# Interface_ETH.net
KiCad netlist of a schematic drawn in EAGLE
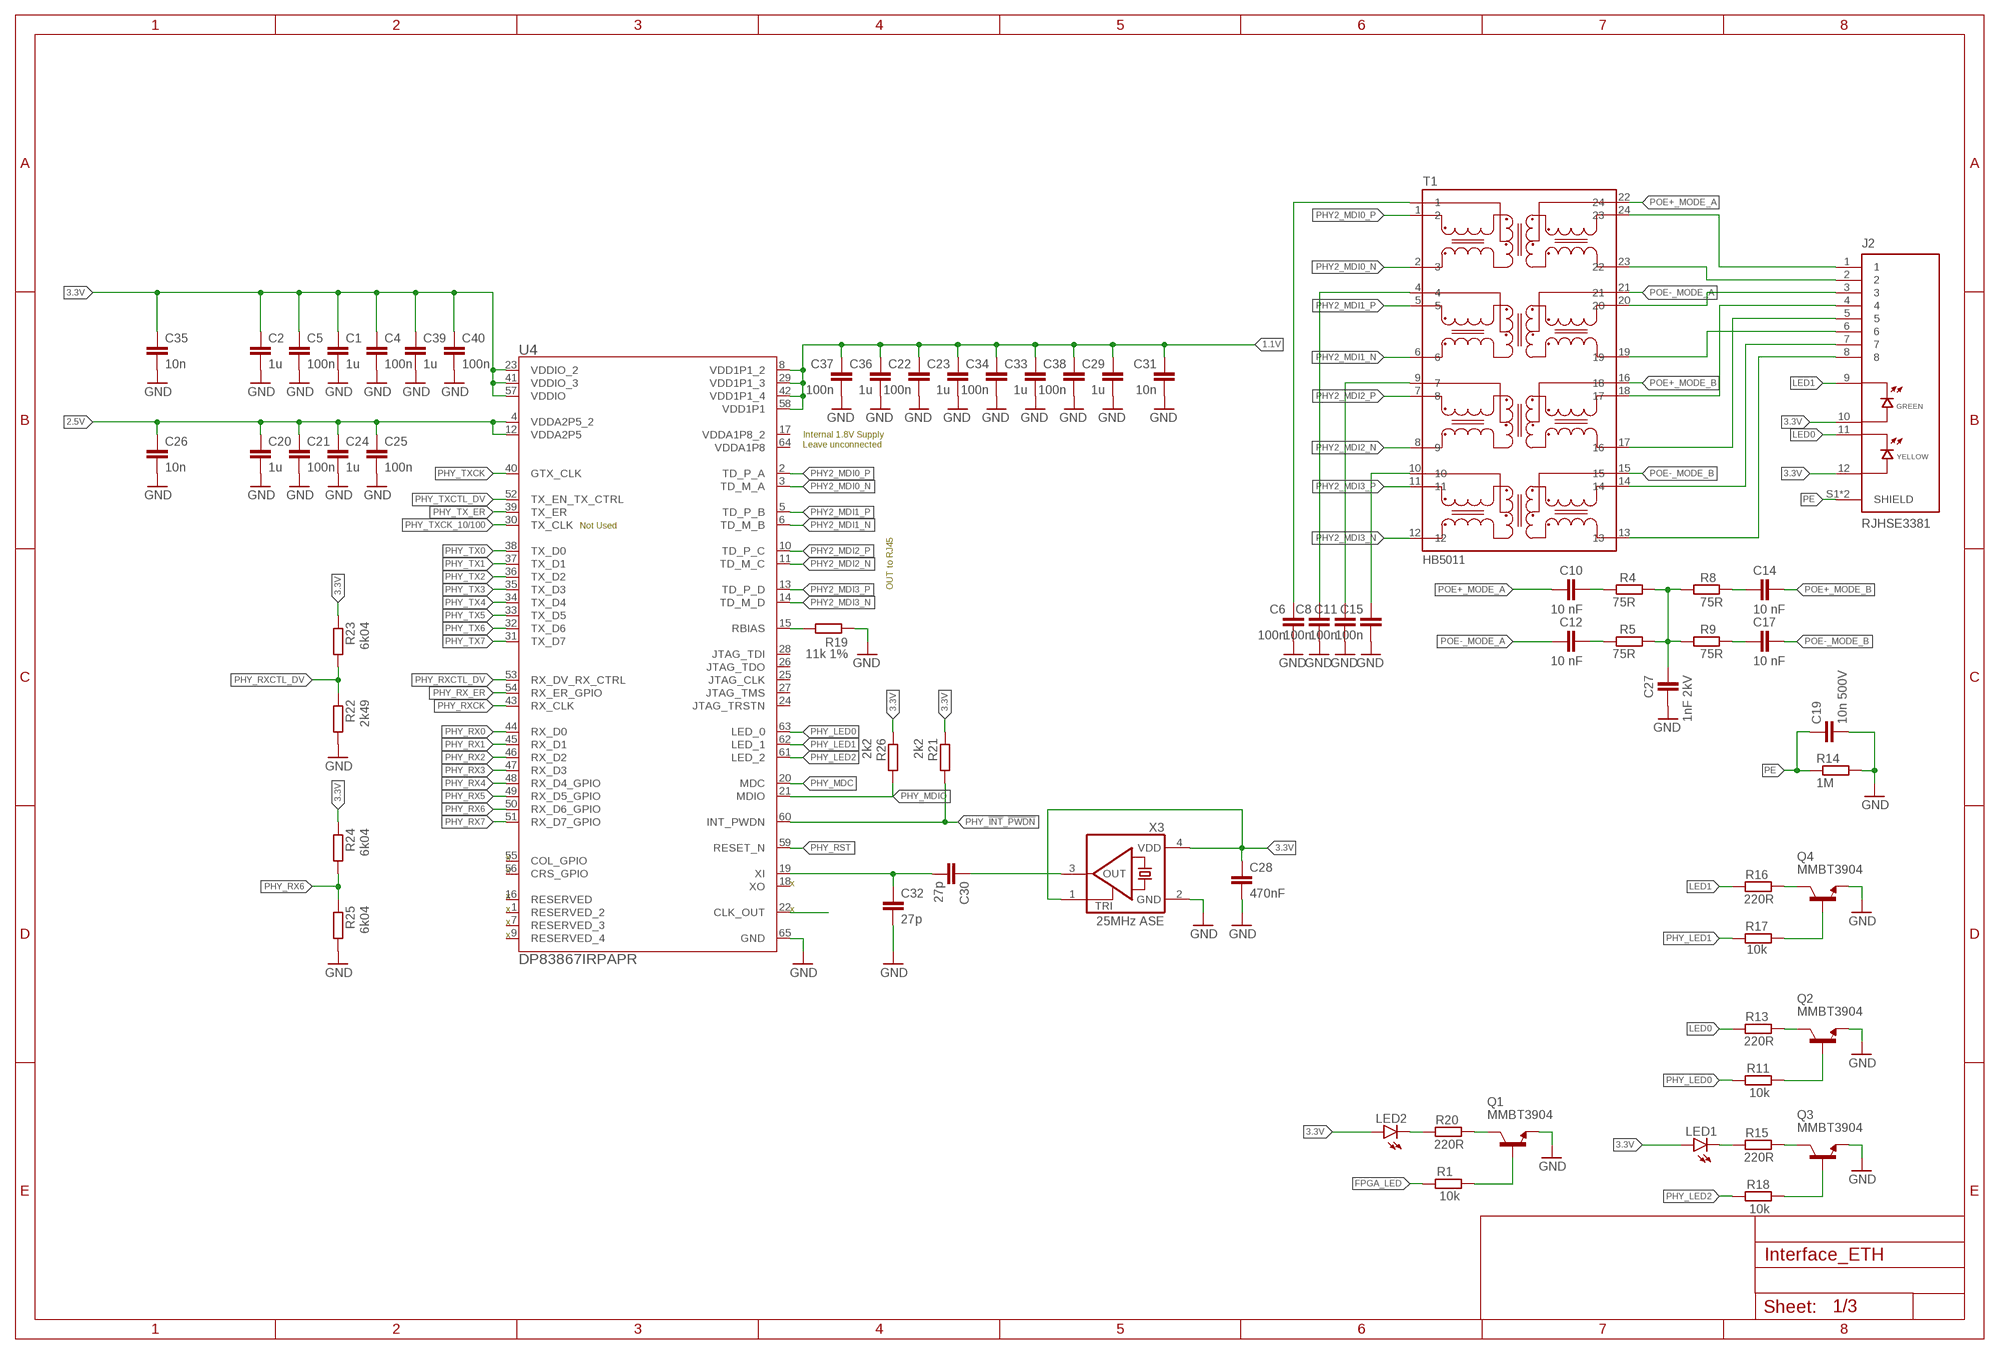
[diagram p0: schematic, sheet 1]
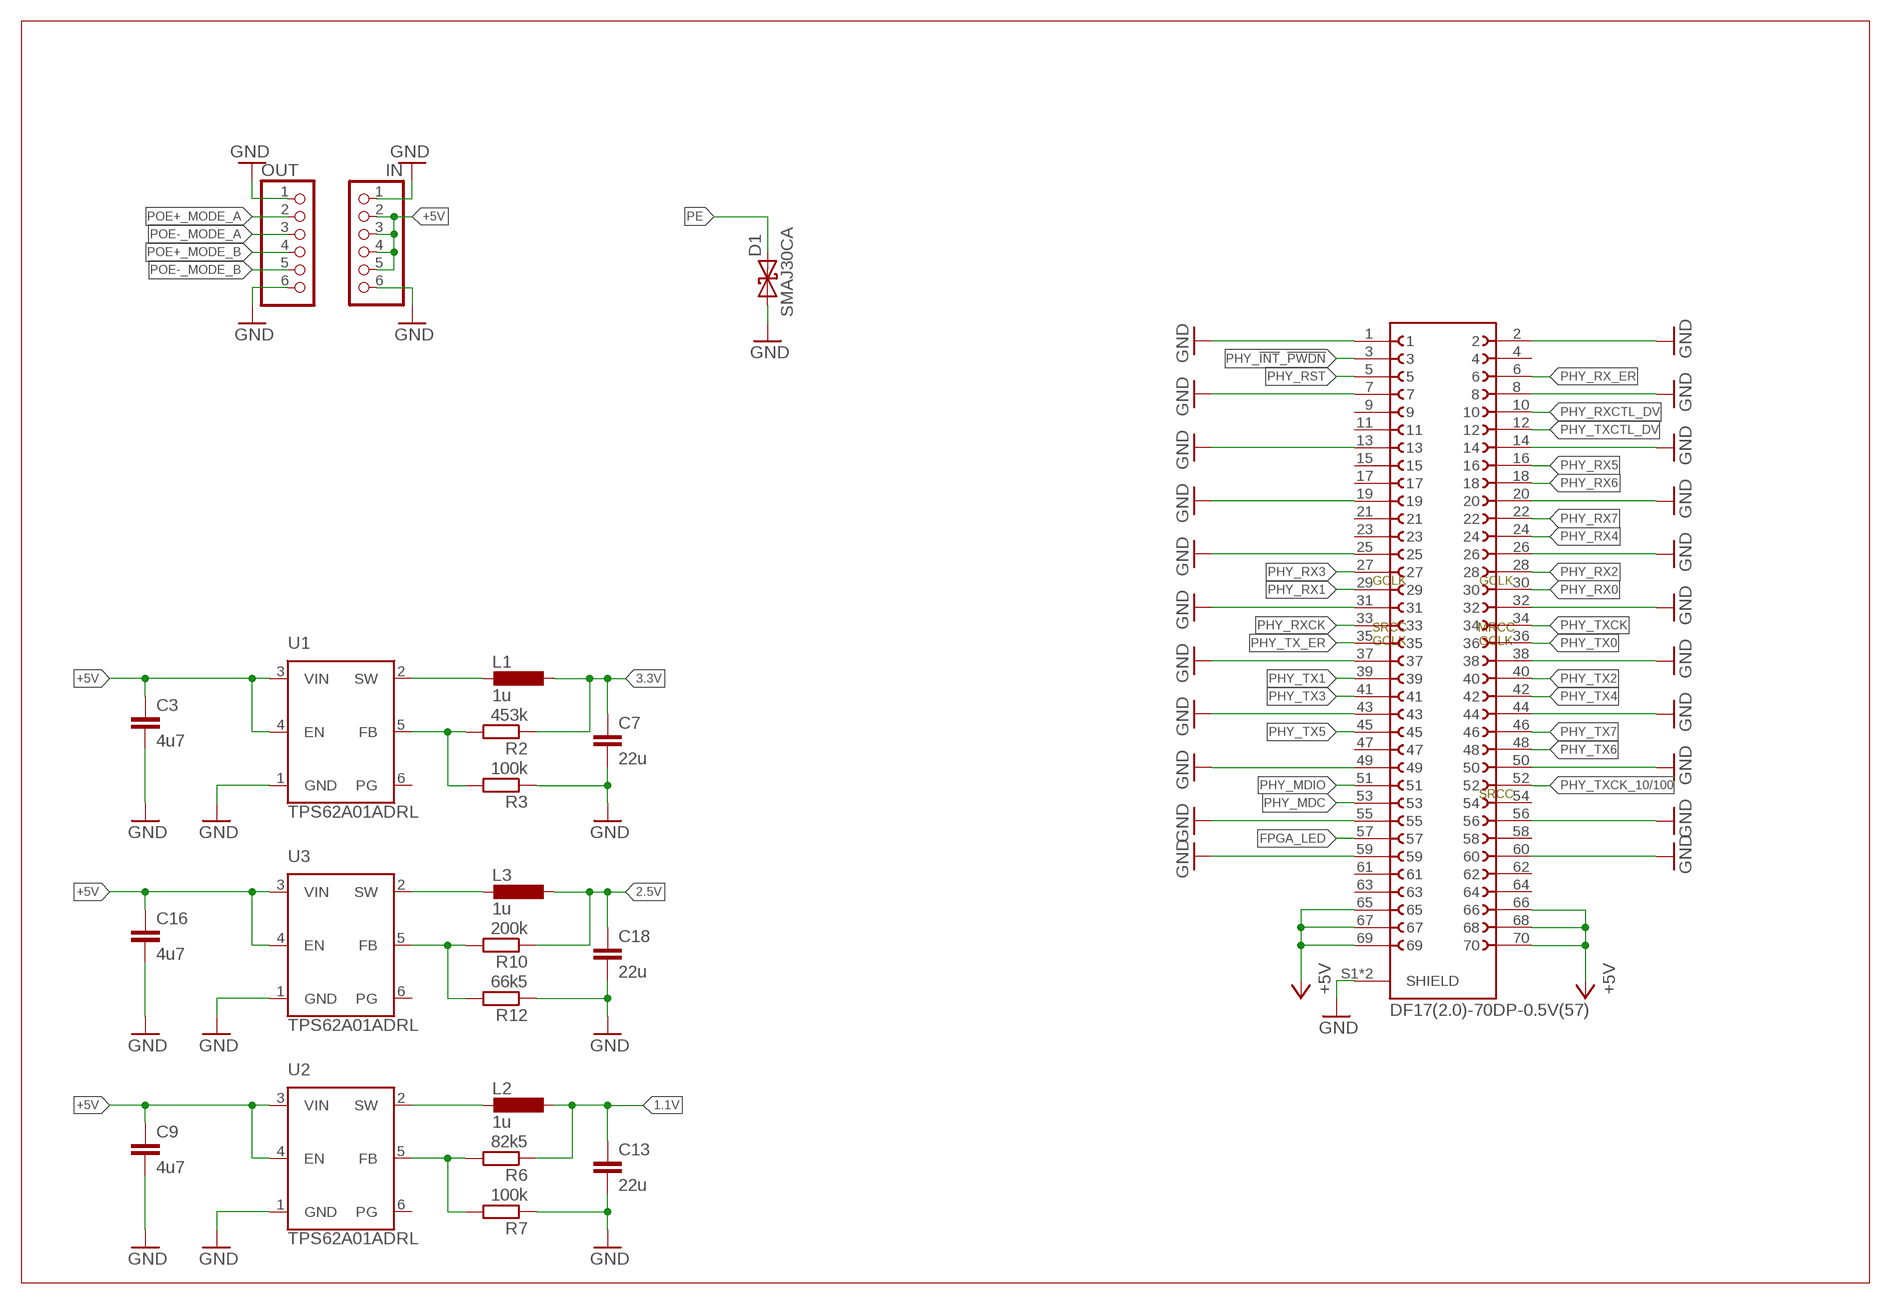
[diagram p1: schematic, sheet 2]

(export (version "E")
  (design (tool "Eeschema 10.0.6"))
  (components
    (comp (ref "C3")
      (value "4u7")
      (footprint "eagle-import:C0603")
      (libsource (lib "eagle-import") (part "C-EUC0603"))
    )
    (comp (ref "C7")
      (value "22u")
      (footprint "eagle-import:C0603")
      (libsource (lib "eagle-import") (part "C-EUC0603"))
    )
    (comp (ref "C9")
      (value "4u7")
      (footprint "eagle-import:C0603")
      (libsource (lib "eagle-import") (part "C-EUC0603"))
    )
    (comp (ref "C13")
      (value "22u")
      (footprint "eagle-import:C0603")
      (libsource (lib "eagle-import") (part "C-EUC0603"))
    )
    (comp (ref "C16")
      (value "4u7")
      (footprint "eagle-import:C0603")
      (libsource (lib "eagle-import") (part "C-EUC0603"))
    )
    (comp (ref "C18")
      (value "22u")
      (footprint "eagle-import:C0603")
      (libsource (lib "eagle-import") (part "C-EUC0603"))
    )
    (comp (ref "D1")
      (value "SMAJ30CA")
      (footprint "eagle-import:DO214AC")
      (libsource (lib "eagle-import") (part "SMAJ_DIODE"))
    )
    (comp (ref "IN")
      (value "PINHD-1X06_2.00")
      (footprint "eagle-import:1X06M")
      (libsource (lib "eagle-import") (part "PINHD-1X06_2.00"))
    )
    (comp (ref "J1")
      (value "DF17(2.0)-70DP-0.5V(57)")
      (footprint "eagle-import:DF17(2.0)-70DP-0.5V(57)")
      (libsource (lib "eagle-import") (part "DF17(2.0)-70DP-0.5V(57)"))
    )
    (comp (ref "L1")
      (value "1u")
      (footprint "eagle-import:L1008")
      (fields (field (name "MPN") "LQM2HPN1R0MG0L"))
      (libsource (lib "eagle-import") (part "L-EU1008"))
    )
    (comp (ref "L2")
      (value "1u")
      (footprint "eagle-import:L1008")
      (fields (field (name "MPN") "LQM2HPN1R0MG0L"))
      (libsource (lib "eagle-import") (part "L-EU1008"))
    )
    (comp (ref "L3")
      (value "1u")
      (footprint "eagle-import:L1008")
      (fields (field (name "MPN") "LQM2HPN1R0MG0L"))
      (libsource (lib "eagle-import") (part "L-EU1008"))
    )
    (comp (ref "OUT")
      (value "PINHD-1X06_2.00")
      (footprint "eagle-import:1X06M")
      (libsource (lib "eagle-import") (part "PINHD-1X06_2.00"))
    )
    (comp (ref "R2")
      (value "453k")
      (footprint "eagle-import:R0402")
      (libsource (lib "eagle-import") (part "rcl_334_R-EU_R0402"))
    )
    (comp (ref "R3")
      (value "100k")
      (footprint "eagle-import:R0402")
      (libsource (lib "eagle-import") (part "rcl_334_R-EU_R0402"))
    )
    (comp (ref "R6")
      (value "82k5")
      (footprint "eagle-import:R0402")
      (libsource (lib "eagle-import") (part "rcl_334_R-EU_R0402"))
    )
    (comp (ref "R7")
      (value "100k")
      (footprint "eagle-import:R0402")
      (libsource (lib "eagle-import") (part "rcl_334_R-EU_R0402"))
    )
    (comp (ref "R10")
      (value "200k")
      (footprint "eagle-import:R0402")
      (libsource (lib "eagle-import") (part "rcl_334_R-EU_R0402"))
    )
    (comp (ref "R12")
      (value "66k5")
      (footprint "eagle-import:R0402")
      (libsource (lib "eagle-import") (part "rcl_334_R-EU_R0402"))
    )
    (comp (ref "U1")
      (value "TPS62A01ADRL")
      (footprint "eagle-import:SOTFL50P160X60-6N")
      (fields (field (name "MANUFACTURER_PART_NUMBER") "TPS62A01ADRLR"))
      (libsource (lib "eagle-import") (part "TPS62A01ADRL"))
    )
    (comp (ref "U2")
      (value "TPS62A01ADRL")
      (footprint "eagle-import:SOTFL50P160X60-6N")
      (fields (field (name "MANUFACTURER_PART_NUMBER") "TPS62A01ADRLR"))
      (libsource (lib "eagle-import") (part "TPS62A01ADRL"))
    )
    (comp (ref "U3")
      (value "TPS62A01ADRL")
      (footprint "eagle-import:SOTFL50P160X60-6N")
      (fields (field (name "MANUFACTURER_PART_NUMBER") "TPS62A01ADRLR"))
      (libsource (lib "eagle-import") (part "TPS62A01ADRL"))
    )
    (comp (ref "C1")
      (value "1u")
      (footprint "eagle-import:C0402")
      (libsource (lib "eagle-import") (part "C-EUC0402"))
    )
    (comp (ref "C2")
      (value "1u")
      (footprint "eagle-import:C0402")
      (libsource (lib "eagle-import") (part "C-EUC0402"))
    )
    (comp (ref "C4")
      (value "100n")
      (footprint "eagle-import:C0402")
      (libsource (lib "eagle-import") (part "C-EUC0402"))
    )
    (comp (ref "C5")
      (value "100n")
      (footprint "eagle-import:C0402")
      (libsource (lib "eagle-import") (part "C-EUC0402"))
    )
    (comp (ref "C6")
      (value "100n")
      (footprint "eagle-import:C0402")
      (libsource (lib "eagle-import") (part "C-EUC0402"))
    )
    (comp (ref "C8")
      (value "100n")
      (footprint "eagle-import:C0402")
      (libsource (lib "eagle-import") (part "C-EUC0402"))
    )
    (comp (ref "C10")
      (value "10 nF")
      (footprint "eagle-import:C0603")
      (libsource (lib "eagle-import") (part "rcl_334_C-EUC0603"))
    )
    (comp (ref "C11")
      (value "100n")
      (footprint "eagle-import:C0402")
      (libsource (lib "eagle-import") (part "C-EUC0402"))
    )
    (comp (ref "C12")
      (value "10 nF")
      (footprint "eagle-import:C0603")
      (libsource (lib "eagle-import") (part "rcl_334_C-EUC0603"))
    )
    (comp (ref "C14")
      (value "10 nF")
      (footprint "eagle-import:C0603")
      (libsource (lib "eagle-import") (part "rcl_334_C-EUC0603"))
    )
    (comp (ref "C15")
      (value "100n")
      (footprint "eagle-import:C0402")
      (libsource (lib "eagle-import") (part "C-EUC0402"))
    )
    (comp (ref "C17")
      (value "10 nF")
      (footprint "eagle-import:C0603")
      (libsource (lib "eagle-import") (part "rcl_334_C-EUC0603"))
    )
    (comp (ref "C19")
      (value "10n 500V")
      (footprint "eagle-import:C0805")
      (libsource (lib "eagle-import") (part "C-EUC0805"))
    )
    (comp (ref "C20")
      (value "1u")
      (footprint "eagle-import:C0402")
      (libsource (lib "eagle-import") (part "C-EUC0402"))
    )
    (comp (ref "C21")
      (value "100n")
      (footprint "eagle-import:C0402")
      (libsource (lib "eagle-import") (part "C-EUC0402"))
    )
    (comp (ref "C22")
      (value "100n")
      (footprint "eagle-import:C0402")
      (libsource (lib "eagle-import") (part "C-EUC0402"))
    )
    (comp (ref "C23")
      (value "1u")
      (footprint "eagle-import:C0402")
      (libsource (lib "eagle-import") (part "C-EUC0402"))
    )
    (comp (ref "C24")
      (value "1u")
      (footprint "eagle-import:C0402")
      (libsource (lib "eagle-import") (part "C-EUC0402"))
    )
    (comp (ref "C25")
      (value "100n")
      (footprint "eagle-import:C0402")
      (libsource (lib "eagle-import") (part "C-EUC0402"))
    )
    (comp (ref "C26")
      (value "10n")
      (footprint "eagle-import:C0402")
      (libsource (lib "eagle-import") (part "C-EUC0402"))
    )
    (comp (ref "C27")
      (value "1nF 2kV")
      (footprint "eagle-import:C1206")
      (libsource (lib "eagle-import") (part "rcl_334_C-EUC1206"))
    )
    (comp (ref "C28")
      (value "470nF")
      (footprint "eagle-import:C0402")
      (libsource (lib "eagle-import") (part "C-EUC0402"))
    )
    (comp (ref "C29")
      (value "1u")
      (footprint "eagle-import:C0402")
      (libsource (lib "eagle-import") (part "C-EUC0402"))
    )
    (comp (ref "C30")
      (value "27p")
      (footprint "eagle-import:C0402")
      (libsource (lib "eagle-import") (part "C-EUC0402"))
    )
    (comp (ref "C31")
      (value "10n")
      (footprint "eagle-import:C0402")
      (libsource (lib "eagle-import") (part "C-EUC0402"))
    )
    (comp (ref "C32")
      (value "27p")
      (footprint "eagle-import:C0402")
      (libsource (lib "eagle-import") (part "C-EUC0402"))
    )
    (comp (ref "C33")
      (value "1u")
      (footprint "eagle-import:C0402")
      (libsource (lib "eagle-import") (part "C-EUC0402"))
    )
    (comp (ref "C34")
      (value "100n")
      (footprint "eagle-import:C0402")
      (libsource (lib "eagle-import") (part "C-EUC0402"))
    )
    (comp (ref "C35")
      (value "10n")
      (footprint "eagle-import:C0402")
      (libsource (lib "eagle-import") (part "C-EUC0402"))
    )
    (comp (ref "C36")
      (value "1u")
      (footprint "eagle-import:C0402")
      (libsource (lib "eagle-import") (part "C-EUC0402"))
    )
    (comp (ref "C37")
      (value "100n")
      (footprint "eagle-import:C0402")
      (libsource (lib "eagle-import") (part "C-EUC0402"))
    )
    (comp (ref "C38")
      (value "100n")
      (footprint "eagle-import:C0402")
      (libsource (lib "eagle-import") (part "C-EUC0402"))
    )
    (comp (ref "C39")
      (value "1u")
      (footprint "eagle-import:C0402")
      (libsource (lib "eagle-import") (part "C-EUC0402"))
    )
    (comp (ref "C40")
      (value "100n")
      (footprint "eagle-import:C0402")
      (libsource (lib "eagle-import") (part "C-EUC0402"))
    )
    (comp (ref "J2")
      (value "RJHSE3381")
      (footprint "eagle-import:AMPHENOL_RJHSE3381")
      (fields (field (name "MANUFACTURER") "Amphenol Connex"))
      (libsource (lib "eagle-import") (part "RJHSE3381"))
    )
    (comp (ref "LED1")
      (value "LEDCHIP-LED0805")
      (footprint "eagle-import:CHIP-LED0805")
      (libsource (lib "eagle-import") (part "LEDCHIP-LED0805"))
    )
    (comp (ref "LED2")
      (value "LEDCHIP-LED0603")
      (footprint "eagle-import:CHIP-LED0603")
      (libsource (lib "eagle-import") (part "LEDCHIP-LED0603"))
    )
    (comp (ref "Q1")
      (value "MMBT3904")
      (footprint "eagle-import:SOT23")
      (libsource (lib "eagle-import") (part "2N3904-MMBT"))
    )
    (comp (ref "Q2")
      (value "MMBT3904")
      (footprint "eagle-import:SOT23")
      (libsource (lib "eagle-import") (part "2N3904-MMBT"))
    )
    (comp (ref "Q3")
      (value "MMBT3904")
      (footprint "eagle-import:SOT23")
      (libsource (lib "eagle-import") (part "2N3904-MMBT"))
    )
    (comp (ref "Q4")
      (value "MMBT3904")
      (footprint "eagle-import:SOT23")
      (libsource (lib "eagle-import") (part "2N3904-MMBT"))
    )
    (comp (ref "R1")
      (value "10k")
      (footprint "eagle-import:R0603")
      (libsource (lib "eagle-import") (part "R-EU_R0603"))
    )
    (comp (ref "R4")
      (value "75R")
      (footprint "eagle-import:R0603")
      (libsource (lib "eagle-import") (part "R-EU_R0603"))
    )
    (comp (ref "R5")
      (value "75R")
      (footprint "eagle-import:R0603")
      (libsource (lib "eagle-import") (part "R-EU_R0603"))
    )
    (comp (ref "R8")
      (value "75R")
      (footprint "eagle-import:R0603")
      (libsource (lib "eagle-import") (part "R-EU_R0603"))
    )
    (comp (ref "R9")
      (value "75R")
      (footprint "eagle-import:R0603")
      (libsource (lib "eagle-import") (part "R-EU_R0603"))
    )
    (comp (ref "R11")
      (value "10k")
      (footprint "eagle-import:R0603")
      (libsource (lib "eagle-import") (part "R-EU_R0603"))
    )
    (comp (ref "R13")
      (value "220R")
      (footprint "eagle-import:R0603")
      (libsource (lib "eagle-import") (part "R-EU_R0603"))
    )
    (comp (ref "R14")
      (value "1M")
      (footprint "eagle-import:R0603")
      (libsource (lib "eagle-import") (part "R-EU_R0603"))
    )
    (comp (ref "R15")
      (value "220R")
      (footprint "eagle-import:R0603")
      (libsource (lib "eagle-import") (part "R-EU_R0603"))
    )
    (comp (ref "R16")
      (value "220R")
      (footprint "eagle-import:R0603")
      (libsource (lib "eagle-import") (part "R-EU_R0603"))
    )
    (comp (ref "R17")
      (value "10k")
      (footprint "eagle-import:R0603")
      (libsource (lib "eagle-import") (part "R-EU_R0603"))
    )
    (comp (ref "R18")
      (value "10k")
      (footprint "eagle-import:R0603")
      (libsource (lib "eagle-import") (part "R-EU_R0603"))
    )
    (comp (ref "R19")
      (value "11k 1%")
      (footprint "eagle-import:R0402")
      (libsource (lib "eagle-import") (part "R-EU_R0402"))
    )
    (comp (ref "R20")
      (value "220R")
      (footprint "eagle-import:R0603")
      (libsource (lib "eagle-import") (part "R-EU_R0603"))
    )
    (comp (ref "R21")
      (value "2k2")
      (footprint "eagle-import:R0402")
      (libsource (lib "eagle-import") (part "R-EU_R0402"))
    )
    (comp (ref "R22")
      (value "2k49")
      (footprint "eagle-import:R0402")
      (libsource (lib "eagle-import") (part "R-EU_R0402"))
    )
    (comp (ref "R23")
      (value "6k04")
      (footprint "eagle-import:R0402")
      (libsource (lib "eagle-import") (part "R-EU_R0402"))
    )
    (comp (ref "R24")
      (value "6k04")
      (footprint "eagle-import:R0402")
      (libsource (lib "eagle-import") (part "R-EU_R0402"))
    )
    (comp (ref "R25")
      (value "6k04")
      (footprint "eagle-import:R0402")
      (libsource (lib "eagle-import") (part "R-EU_R0402"))
    )
    (comp (ref "R26")
      (value "2k2")
      (footprint "eagle-import:R0402")
      (libsource (lib "eagle-import") (part "R-EU_R0402"))
    )
    (comp (ref "T1")
      (value "HB5011")
      (footprint "eagle-import:HB5011")
      (libsource (lib "eagle-import") (part "HB5011"))
    )
    (comp (ref "U4")
      (value "DP83867IRPAPR")
      (footprint "eagle-import:PAP0064M_N")
      (libsource (lib "eagle-import") (part "DP83867IRPAPR"))
    )
    (comp (ref "X3")
      (value "25MHz ASE")
      (footprint "eagle-import:ASE")
      (libsource (lib "eagle-import") (part "ASE"))
    )
  )
  (nets
    (net (code "1") (name "+5V") (class "Default")
      (node (ref "C16") (pin "1") (pinfunction "1_1") (pintype "passive"))
      (node (ref "C3") (pin "1") (pinfunction "1_1") (pintype "passive"))
      (node (ref "C9") (pin "1") (pinfunction "1_1") (pintype "passive"))
      (node (ref "IN") (pin "2") (pinfunction "2_2") (pintype "passive"))
      (node (ref "IN") (pin "3") (pinfunction "3_3") (pintype "passive"))
      (node (ref "IN") (pin "4") (pinfunction "4_4") (pintype "passive"))
      (node (ref "IN") (pin "5") (pinfunction "5_5") (pintype "passive"))
      (node (ref "J1") (pin "65") (pinfunction "65_65") (pintype "passive"))
      (node (ref "J1") (pin "66") (pinfunction "66_66") (pintype "passive"))
      (node (ref "J1") (pin "67") (pinfunction "67_67") (pintype "passive"))
      (node (ref "J1") (pin "68") (pinfunction "68_68") (pintype "passive"))
      (node (ref "J1") (pin "69") (pinfunction "69_69") (pintype "passive"))
      (node (ref "J1") (pin "70") (pinfunction "70_70") (pintype "passive"))
      (node (ref "U1") (pin "3") (pinfunction "VIN_3") (pintype "bidirectional"))
      (node (ref "U1") (pin "4") (pinfunction "EN_4") (pintype "bidirectional"))
      (node (ref "U2") (pin "3") (pinfunction "VIN_3") (pintype "bidirectional"))
      (node (ref "U2") (pin "4") (pinfunction "EN_4") (pintype "bidirectional"))
      (node (ref "U3") (pin "3") (pinfunction "VIN_3") (pintype "bidirectional"))
      (node (ref "U3") (pin "4") (pinfunction "EN_4") (pintype "bidirectional"))
    )
    (net (code "2") (name "1.1V") (class "Default")
      (node (ref "C13") (pin "1") (pinfunction "1_1") (pintype "passive"))
      (node (ref "C22") (pin "1") (pinfunction "1_1") (pintype "passive"))
      (node (ref "C23") (pin "1") (pinfunction "1_1") (pintype "passive"))
      (node (ref "C29") (pin "1") (pinfunction "1_1") (pintype "passive"))
      (node (ref "C31") (pin "1") (pinfunction "1_1") (pintype "passive"))
      (node (ref "C33") (pin "1") (pinfunction "1_1") (pintype "passive"))
      (node (ref "C34") (pin "1") (pinfunction "1_1") (pintype "passive"))
      (node (ref "C36") (pin "1") (pinfunction "1_1") (pintype "passive"))
      (node (ref "C37") (pin "1") (pinfunction "1_1") (pintype "passive"))
      (node (ref "C38") (pin "1") (pinfunction "1_1") (pintype "passive"))
      (node (ref "L2") (pin "1") (pinfunction "1_1") (pintype "passive"))
      (node (ref "R6") (pin "1") (pinfunction "1_1") (pintype "passive"))
      (node (ref "U4") (pin "29") (pinfunction "VDD1P1_3_29") (pintype "power_in"))
      (node (ref "U4") (pin "42") (pinfunction "VDD1P1_4_42") (pintype "power_in"))
      (node (ref "U4") (pin "58") (pinfunction "VDD1P1_58") (pintype "power_in"))
      (node (ref "U4") (pin "8") (pinfunction "VDD1P1_2_8") (pintype "power_in"))
    )
    (net (code "3") (name "2.5V") (class "Default")
      (node (ref "C18") (pin "1") (pinfunction "1_1") (pintype "passive"))
      (node (ref "C20") (pin "1") (pinfunction "1_1") (pintype "passive"))
      (node (ref "C21") (pin "1") (pinfunction "1_1") (pintype "passive"))
      (node (ref "C24") (pin "1") (pinfunction "1_1") (pintype "passive"))
      (node (ref "C25") (pin "1") (pinfunction "1_1") (pintype "passive"))
      (node (ref "C26") (pin "1") (pinfunction "1_1") (pintype "passive"))
      (node (ref "L3") (pin "1") (pinfunction "1_1") (pintype "passive"))
      (node (ref "R10") (pin "1") (pinfunction "1_1") (pintype "passive"))
      (node (ref "U4") (pin "12") (pinfunction "VDDA2P5_12") (pintype "power_in"))
      (node (ref "U4") (pin "4") (pinfunction "VDDA2P5_2_4") (pintype "power_in"))
    )
    (net (code "4") (name "3.3V") (class "Default")
      (node (ref "C1") (pin "1") (pinfunction "1_1") (pintype "passive"))
      (node (ref "C2") (pin "1") (pinfunction "1_1") (pintype "passive"))
      (node (ref "C28") (pin "1") (pinfunction "1_1") (pintype "passive"))
      (node (ref "C35") (pin "1") (pinfunction "1_1") (pintype "passive"))
      (node (ref "C39") (pin "1") (pinfunction "1_1") (pintype "passive"))
      (node (ref "C4") (pin "1") (pinfunction "1_1") (pintype "passive"))
      (node (ref "C40") (pin "1") (pinfunction "1_1") (pintype "passive"))
      (node (ref "C5") (pin "1") (pinfunction "1_1") (pintype "passive"))
      (node (ref "C7") (pin "1") (pinfunction "1_1") (pintype "passive"))
      (node (ref "J2") (pin "10") (pinfunction "10_10") (pintype "passive"))
      (node (ref "J2") (pin "12") (pinfunction "12_12") (pintype "passive"))
      (node (ref "L1") (pin "1") (pinfunction "1_1") (pintype "passive"))
      (node (ref "LED1") (pin "A") (pinfunction "A_A") (pintype "passive"))
      (node (ref "LED2") (pin "A") (pinfunction "A_A") (pintype "passive"))
      (node (ref "R2") (pin "1") (pinfunction "1_1") (pintype "passive"))
      (node (ref "R21") (pin "1") (pinfunction "1_1") (pintype "passive"))
      (node (ref "R23") (pin "1") (pinfunction "1_1") (pintype "passive"))
      (node (ref "R24") (pin "1") (pinfunction "1_1") (pintype "passive"))
      (node (ref "R26") (pin "1") (pinfunction "1_1") (pintype "passive"))
      (node (ref "U4") (pin "23") (pinfunction "VDDIO_2_23") (pintype "power_in"))
      (node (ref "U4") (pin "41") (pinfunction "VDDIO_3_41") (pintype "power_in"))
      (node (ref "U4") (pin "57") (pinfunction "VDDIO_57") (pintype "power_in"))
      (node (ref "X3") (pin "1") (pinfunction "TRI_1") (pintype "input"))
      (node (ref "X3") (pin "4") (pinfunction "VDD_4") (pintype "power_in"))
    )
    (net (code "5") (name "FPGA_LED") (class "Default")
      (node (ref "J1") (pin "57") (pinfunction "57_57") (pintype "passive"))
      (node (ref "R1") (pin "1") (pinfunction "1_1") (pintype "passive"))
    )
    (net (code "6") (name "GND") (class "Default")
      (node (ref "C1") (pin "2") (pinfunction "2_2") (pintype "passive"))
      (node (ref "C11") (pin "2") (pinfunction "2_2") (pintype "passive"))
      (node (ref "C13") (pin "2") (pinfunction "2_2") (pintype "passive"))
      (node (ref "C15") (pin "2") (pinfunction "2_2") (pintype "passive"))
      (node (ref "C16") (pin "2") (pinfunction "2_2") (pintype "passive"))
      (node (ref "C18") (pin "2") (pinfunction "2_2") (pintype "passive"))
      (node (ref "C19") (pin "2") (pinfunction "2_2") (pintype "passive"))
      (node (ref "C2") (pin "2") (pinfunction "2_2") (pintype "passive"))
      (node (ref "C20") (pin "2") (pinfunction "2_2") (pintype "passive"))
      (node (ref "C21") (pin "2") (pinfunction "2_2") (pintype "passive"))
      (node (ref "C22") (pin "2") (pinfunction "2_2") (pintype "passive"))
      (node (ref "C23") (pin "2") (pinfunction "2_2") (pintype "passive"))
      (node (ref "C24") (pin "2") (pinfunction "2_2") (pintype "passive"))
      (node (ref "C25") (pin "2") (pinfunction "2_2") (pintype "passive"))
      (node (ref "C26") (pin "2") (pinfunction "2_2") (pintype "passive"))
      (node (ref "C27") (pin "2") (pinfunction "2_2") (pintype "passive"))
      (node (ref "C28") (pin "2") (pinfunction "2_2") (pintype "passive"))
      (node (ref "C29") (pin "2") (pinfunction "2_2") (pintype "passive"))
      (node (ref "C3") (pin "2") (pinfunction "2_2") (pintype "passive"))
      (node (ref "C31") (pin "2") (pinfunction "2_2") (pintype "passive"))
      (node (ref "C32") (pin "2") (pinfunction "2_2") (pintype "passive"))
      (node (ref "C33") (pin "2") (pinfunction "2_2") (pintype "passive"))
      (node (ref "C34") (pin "2") (pinfunction "2_2") (pintype "passive"))
      (node (ref "C35") (pin "2") (pinfunction "2_2") (pintype "passive"))
      (node (ref "C36") (pin "2") (pinfunction "2_2") (pintype "passive"))
      (node (ref "C37") (pin "2") (pinfunction "2_2") (pintype "passive"))
      (node (ref "C38") (pin "2") (pinfunction "2_2") (pintype "passive"))
      (node (ref "C39") (pin "2") (pinfunction "2_2") (pintype "passive"))
      (node (ref "C4") (pin "2") (pinfunction "2_2") (pintype "passive"))
      (node (ref "C40") (pin "2") (pinfunction "2_2") (pintype "passive"))
      (node (ref "C5") (pin "2") (pinfunction "2_2") (pintype "passive"))
      (node (ref "C6") (pin "2") (pinfunction "2_2") (pintype "passive"))
      (node (ref "C7") (pin "2") (pinfunction "2_2") (pintype "passive"))
      (node (ref "C8") (pin "2") (pinfunction "2_2") (pintype "passive"))
      (node (ref "C9") (pin "2") (pinfunction "2_2") (pintype "passive"))
      (node (ref "D1") (pin "A") (pinfunction "1_A") (pintype "passive"))
      (node (ref "IN") (pin "1") (pinfunction "1_1") (pintype "passive"))
      (node (ref "IN") (pin "6") (pinfunction "6_6") (pintype "passive"))
      (node (ref "J1") (pin "1") (pinfunction "1_1") (pintype "passive"))
      (node (ref "J1") (pin "13") (pinfunction "13_13") (pintype "passive"))
      (node (ref "J1") (pin "14") (pinfunction "14_14") (pintype "passive"))
      (node (ref "J1") (pin "19") (pinfunction "19_19") (pintype "passive"))
      (node (ref "J1") (pin "2") (pinfunction "2_2") (pintype "passive"))
      (node (ref "J1") (pin "20") (pinfunction "20_20") (pintype "passive"))
      (node (ref "J1") (pin "25") (pinfunction "25_25") (pintype "passive"))
      (node (ref "J1") (pin "26") (pinfunction "26_26") (pintype "passive"))
      (node (ref "J1") (pin "31") (pinfunction "31_31") (pintype "passive"))
      (node (ref "J1") (pin "32") (pinfunction "32_32") (pintype "passive"))
      (node (ref "J1") (pin "37") (pinfunction "37_37") (pintype "passive"))
      (node (ref "J1") (pin "38") (pinfunction "38_38") (pintype "passive"))
      (node (ref "J1") (pin "43") (pinfunction "43_43") (pintype "passive"))
      (node (ref "J1") (pin "44") (pinfunction "44_44") (pintype "passive"))
      (node (ref "J1") (pin "49") (pinfunction "49_49") (pintype "passive"))
      (node (ref "J1") (pin "50") (pinfunction "50_50") (pintype "passive"))
      (node (ref "J1") (pin "55") (pinfunction "55_55") (pintype "passive"))
      (node (ref "J1") (pin "56") (pinfunction "56_56") (pintype "passive"))
      (node (ref "J1") (pin "59") (pinfunction "59_59") (pintype "passive"))
      (node (ref "J1") (pin "60") (pinfunction "60_60") (pintype "passive"))
      (node (ref "J1") (pin "7") (pinfunction "7_7") (pintype "passive"))
      (node (ref "J1") (pin "8") (pinfunction "8_8") (pintype "passive"))
      (node (ref "J1") (pin "S1") (pinfunction "SHIELD_S1") (pintype "passive"))
      (node (ref "J1") (pin "S2") (pinfunction "SHIELD_S2") (pintype "passive"))
      (node (ref "OUT") (pin "1") (pinfunction "1_1") (pintype "passive"))
      (node (ref "OUT") (pin "6") (pinfunction "6_6") (pintype "passive"))
      (node (ref "Q1") (pin "2") (pinfunction "E_2") (pintype "passive"))
      (node (ref "Q2") (pin "2") (pinfunction "E_2") (pintype "passive"))
      (node (ref "Q3") (pin "2") (pinfunction "E_2") (pintype "passive"))
      (node (ref "Q4") (pin "2") (pinfunction "E_2") (pintype "passive"))
      (node (ref "R12") (pin "1") (pinfunction "1_1") (pintype "passive"))
      (node (ref "R14") (pin "2") (pinfunction "2_2") (pintype "passive"))
      (node (ref "R19") (pin "1") (pinfunction "1_1") (pintype "passive"))
      (node (ref "R22") (pin "2") (pinfunction "2_2") (pintype "passive"))
      (node (ref "R25") (pin "2") (pinfunction "2_2") (pintype "passive"))
      (node (ref "R3") (pin "1") (pinfunction "1_1") (pintype "passive"))
      (node (ref "R7") (pin "1") (pinfunction "1_1") (pintype "passive"))
      (node (ref "U1") (pin "1") (pinfunction "GND_1") (pintype "bidirectional"))
      (node (ref "U2") (pin "1") (pinfunction "GND_1") (pintype "bidirectional"))
      (node (ref "U3") (pin "1") (pinfunction "GND_1") (pintype "bidirectional"))
      (node (ref "U4") (pin "65") (pinfunction "GND_65") (pintype "power_in"))
      (node (ref "X3") (pin "2") (pinfunction "GND_2") (pintype "power_in"))
    )
    (net (code "7") (name "LED0") (class "Default")
      (node (ref "J2") (pin "11") (pinfunction "11_11") (pintype "passive"))
      (node (ref "R13") (pin "1") (pinfunction "1_1") (pintype "passive"))
    )
    (net (code "8") (name "LED1") (class "Default")
      (node (ref "J2") (pin "9") (pinfunction "9_9") (pintype "passive"))
      (node (ref "R16") (pin "1") (pinfunction "1_1") (pintype "passive"))
    )
    (net (code "9") (name "Net-(C8-Pad1)") (class "Default")
      (node (ref "C8") (pin "1") (pinfunction "1_1") (pintype "passive"))
      (node (ref "T1") (pin "4") (pinfunction "4_4") (pintype "bidirectional"))
    )
    (net (code "10") (name "Net-(C10-Pad1)") (class "Default")
      (node (ref "C10") (pin "1") (pinfunction "1_1") (pintype "passive"))
      (node (ref "R4") (pin "2") (pinfunction "2_2") (pintype "passive"))
    )
    (net (code "11") (name "Net-(C12-Pad1)") (class "Default")
      (node (ref "C12") (pin "1") (pinfunction "1_1") (pintype "passive"))
      (node (ref "R5") (pin "2") (pinfunction "2_2") (pintype "passive"))
    )
    (net (code "12") (name "Net-(C14-Pad1)") (class "Default")
      (node (ref "C14") (pin "1") (pinfunction "1_1") (pintype "passive"))
      (node (ref "R8") (pin "2") (pinfunction "2_2") (pintype "passive"))
    )
    (net (code "13") (name "Net-(C15-Pad1)") (class "Default")
      (node (ref "C15") (pin "1") (pinfunction "1_1") (pintype "passive"))
      (node (ref "T1") (pin "10") (pinfunction "10_10") (pintype "bidirectional"))
    )
    (net (code "14") (name "Net-(C17-Pad1)") (class "Default")
      (node (ref "C17") (pin "1") (pinfunction "1_1") (pintype "passive"))
      (node (ref "R9") (pin "2") (pinfunction "2_2") (pintype "passive"))
    )
    (net (code "15") (name "Net-(C27-Pad1)") (class "Default")
      (node (ref "C27") (pin "1") (pinfunction "1_1") (pintype "passive"))
      (node (ref "R4") (pin "1") (pinfunction "1_1") (pintype "passive"))
      (node (ref "R5") (pin "1") (pinfunction "1_1") (pintype "passive"))
      (node (ref "R8") (pin "1") (pinfunction "1_1") (pintype "passive"))
      (node (ref "R9") (pin "1") (pinfunction "1_1") (pintype "passive"))
    )
    (net (code "16") (name "Net-(J2-Pad3)") (class "Default")
      (node (ref "J2") (pin "3") (pinfunction "3_3") (pintype "passive"))
      (node (ref "T1") (pin "20") (pinfunction "20_20") (pintype "bidirectional"))
    )
    (net (code "17") (name "Net-(J2-Pad6)") (class "Default")
      (node (ref "J2") (pin "6") (pinfunction "6_6") (pintype "passive"))
      (node (ref "T1") (pin "19") (pinfunction "19_19") (pintype "bidirectional"))
    )
    (net (code "18") (name "Net-(J2-Pad7)") (class "Default")
      (node (ref "J2") (pin "7") (pinfunction "7_7") (pintype "passive"))
      (node (ref "T1") (pin "14") (pinfunction "14_14") (pintype "bidirectional"))
    )
    (net (code "19") (name "Net-(J2-Pad8)") (class "Default")
      (node (ref "J2") (pin "8") (pinfunction "8_8") (pintype "passive"))
      (node (ref "T1") (pin "13") (pinfunction "13_13") (pintype "bidirectional"))
    )
    (net (code "20") (name "Net-(LED1-PadC)") (class "Default")
      (node (ref "LED1") (pin "C") (pinfunction "C_C") (pintype "passive"))
      (node (ref "R15") (pin "1") (pinfunction "1_1") (pintype "passive"))
    )
    (net (code "21") (name "Net-(LED2-PadC)") (class "Default")
      (node (ref "LED2") (pin "C") (pinfunction "C_C") (pintype "passive"))
      (node (ref "R20") (pin "1") (pinfunction "1_1") (pintype "passive"))
    )
    (net (code "22") (name "Net-(Q1-B)") (class "Default")
      (node (ref "Q1") (pin "1") (pinfunction "B_1") (pintype "passive"))
      (node (ref "R1") (pin "2") (pinfunction "2_2") (pintype "passive"))
    )
    (net (code "23") (name "Net-(Q1-C)") (class "Default")
      (node (ref "Q1") (pin "3") (pinfunction "C_3") (pintype "passive"))
      (node (ref "R20") (pin "2") (pinfunction "2_2") (pintype "passive"))
    )
    (net (code "24") (name "Net-(Q2-B)") (class "Default")
      (node (ref "Q2") (pin "1") (pinfunction "B_1") (pintype "passive"))
      (node (ref "R11") (pin "2") (pinfunction "2_2") (pintype "passive"))
    )
    (net (code "25") (name "Net-(Q2-C)") (class "Default")
      (node (ref "Q2") (pin "3") (pinfunction "C_3") (pintype "passive"))
      (node (ref "R13") (pin "2") (pinfunction "2_2") (pintype "passive"))
    )
    (net (code "26") (name "Net-(Q3-B)") (class "Default")
      (node (ref "Q3") (pin "1") (pinfunction "B_1") (pintype "passive"))
      (node (ref "R18") (pin "2") (pinfunction "2_2") (pintype "passive"))
    )
    (net (code "27") (name "Net-(Q3-C)") (class "Default")
      (node (ref "Q3") (pin "3") (pinfunction "C_3") (pintype "passive"))
      (node (ref "R15") (pin "2") (pinfunction "2_2") (pintype "passive"))
    )
    (net (code "28") (name "Net-(Q4-B)") (class "Default")
      (node (ref "Q4") (pin "1") (pinfunction "B_1") (pintype "passive"))
      (node (ref "R17") (pin "2") (pinfunction "2_2") (pintype "passive"))
    )
    (net (code "29") (name "Net-(Q4-C)") (class "Default")
      (node (ref "Q4") (pin "3") (pinfunction "C_3") (pintype "passive"))
      (node (ref "R16") (pin "2") (pinfunction "2_2") (pintype "passive"))
    )
    (net (code "30") (name "Net-(T1-1)") (class "Default")
      (node (ref "C6") (pin "1") (pinfunction "1_1") (pintype "passive"))
      (node (ref "T1") (pin "3") (pinfunction "1_3") (pintype "bidirectional"))
    )
    (net (code "31") (name "Net-(T1-7)") (class "Default")
      (node (ref "C11") (pin "1") (pinfunction "1_1") (pintype "passive"))
      (node (ref "T1") (pin "9") (pinfunction "7_9") (pintype "bidirectional"))
    )
    (net (code "32") (name "Net-(T1-16)") (class "Default")
      (node (ref "J2") (pin "5") (pinfunction "5_5") (pintype "passive"))
      (node (ref "T1") (pin "17") (pinfunction "16_17") (pintype "bidirectional"))
    )
    (net (code "33") (name "Net-(T1-17)") (class "Default")
      (node (ref "J2") (pin "4") (pinfunction "4_4") (pintype "passive"))
      (node (ref "T1") (pin "18") (pinfunction "17_18") (pintype "bidirectional"))
    )
    (net (code "34") (name "Net-(T1-22)") (class "Default")
      (node (ref "J2") (pin "2") (pinfunction "2_2") (pintype "passive"))
      (node (ref "T1") (pin "23") (pinfunction "22_23") (pintype "bidirectional"))
    )
    (net (code "35") (name "Net-(T1-23)") (class "Default")
      (node (ref "J2") (pin "1") (pinfunction "1_1") (pintype "passive"))
      (node (ref "T1") (pin "24") (pinfunction "23_24") (pintype "bidirectional"))
    )
    (net (code "36") (name "Net-(U1-FB)") (class "Default")
      (node (ref "R2") (pin "2") (pinfunction "2_2") (pintype "passive"))
      (node (ref "R3") (pin "2") (pinfunction "2_2") (pintype "passive"))
      (node (ref "U1") (pin "5") (pinfunction "FB_5") (pintype "bidirectional"))
    )
    (net (code "37") (name "Net-(U1-SW)") (class "Default")
      (node (ref "L1") (pin "2") (pinfunction "2_2") (pintype "passive"))
      (node (ref "U1") (pin "2") (pinfunction "SW_2") (pintype "bidirectional"))
    )
    (net (code "38") (name "Net-(U2-FB)") (class "Default")
      (node (ref "R6") (pin "2") (pinfunction "2_2") (pintype "passive"))
      (node (ref "R7") (pin "2") (pinfunction "2_2") (pintype "passive"))
      (node (ref "U2") (pin "5") (pinfunction "FB_5") (pintype "bidirectional"))
    )
    (net (code "39") (name "Net-(U2-SW)") (class "Default")
      (node (ref "L2") (pin "2") (pinfunction "2_2") (pintype "passive"))
      (node (ref "U2") (pin "2") (pinfunction "SW_2") (pintype "bidirectional"))
    )
    (net (code "40") (name "Net-(U3-FB)") (class "Default")
      (node (ref "R10") (pin "2") (pinfunction "2_2") (pintype "passive"))
      (node (ref "R12") (pin "2") (pinfunction "2_2") (pintype "passive"))
      (node (ref "U3") (pin "5") (pinfunction "FB_5") (pintype "bidirectional"))
    )
    (net (code "41") (name "Net-(U3-SW)") (class "Default")
      (node (ref "L3") (pin "2") (pinfunction "2_2") (pintype "passive"))
      (node (ref "U3") (pin "2") (pinfunction "SW_2") (pintype "bidirectional"))
    )
    (net (code "42") (name "Net-(U4-RBIAS)") (class "Default")
      (node (ref "R19") (pin "2") (pinfunction "2_2") (pintype "passive"))
      (node (ref "U4") (pin "15") (pinfunction "RBIAS_15") (pintype "passive"))
    )
    (net (code "43") (name "Net-(U4-XI)") (class "Default")
      (node (ref "C30") (pin "2") (pinfunction "2_2") (pintype "passive"))
      (node (ref "C32") (pin "1") (pinfunction "1_1") (pintype "passive"))
      (node (ref "U4") (pin "19") (pinfunction "XI_19") (pintype "passive"))
    )
    (net (code "44") (name "Net-(X3-OUT)") (class "Default")
      (node (ref "C30") (pin "1") (pinfunction "1_1") (pintype "passive"))
      (node (ref "X3") (pin "3") (pinfunction "OUT_3") (pintype "output"))
    )
    (net (code "45") (name "PE") (class "Default")
      (node (ref "C19") (pin "1") (pinfunction "1_1") (pintype "passive"))
      (node (ref "D1") (pin "C") (pinfunction "2_C") (pintype "passive"))
      (node (ref "J2") (pin "S1") (pinfunction "SHIELD_S1") (pintype "passive"))
      (node (ref "J2") (pin "S2") (pinfunction "SHIELD_S2") (pintype "passive"))
      (node (ref "R14") (pin "1") (pinfunction "1_1") (pintype "passive"))
    )
    (net (code "46") (name "PHY2_MDI0_N") (class "Default")
      (node (ref "T1") (pin "2") (pinfunction "3_2") (pintype "bidirectional"))
      (node (ref "U4") (pin "3") (pinfunction "TD_M_A_3") (pintype "bidirectional"))
    )
    (net (code "47") (name "PHY2_MDI0_P") (class "Default")
      (node (ref "T1") (pin "1") (pinfunction "2_1") (pintype "bidirectional"))
      (node (ref "U4") (pin "2") (pinfunction "TD_P_A_2") (pintype "bidirectional"))
    )
    (net (code "48") (name "PHY2_MDI1_N") (class "Default")
      (node (ref "T1") (pin "6") (pinfunction "6_6") (pintype "bidirectional"))
      (node (ref "U4") (pin "6") (pinfunction "TD_M_B_6") (pintype "bidirectional"))
    )
    (net (code "49") (name "PHY2_MDI1_P") (class "Default")
      (node (ref "T1") (pin "5") (pinfunction "5_5") (pintype "bidirectional"))
      (node (ref "U4") (pin "5") (pinfunction "TD_P_B_5") (pintype "bidirectional"))
    )
    (net (code "50") (name "PHY2_MDI2_N") (class "Default")
      (node (ref "T1") (pin "8") (pinfunction "9_8") (pintype "bidirectional"))
      (node (ref "U4") (pin "11") (pinfunction "TD_M_C_11") (pintype "bidirectional"))
    )
    (net (code "51") (name "PHY2_MDI2_P") (class "Default")
      (node (ref "T1") (pin "7") (pinfunction "8_7") (pintype "bidirectional"))
      (node (ref "U4") (pin "10") (pinfunction "TD_P_C_10") (pintype "bidirectional"))
    )
    (net (code "52") (name "PHY2_MDI3_N") (class "Default")
      (node (ref "T1") (pin "12") (pinfunction "12_12") (pintype "bidirectional"))
      (node (ref "U4") (pin "14") (pinfunction "TD_M_D_14") (pintype "bidirectional"))
    )
    (net (code "53") (name "PHY2_MDI3_P") (class "Default")
      (node (ref "T1") (pin "11") (pinfunction "11_11") (pintype "bidirectional"))
      (node (ref "U4") (pin "13") (pinfunction "TD_P_D_13") (pintype "bidirectional"))
    )
    (net (code "54") (name "PHY_LED0") (class "Default")
      (node (ref "R11") (pin "1") (pinfunction "1_1") (pintype "passive"))
      (node (ref "U4") (pin "63") (pinfunction "LED_0_63") (pintype "bidirectional"))
    )
    (net (code "55") (name "PHY_LED1") (class "Default")
      (node (ref "R17") (pin "1") (pinfunction "1_1") (pintype "passive"))
      (node (ref "U4") (pin "62") (pinfunction "LED_1_62") (pintype "bidirectional"))
    )
    (net (code "56") (name "PHY_LED2") (class "Default")
      (node (ref "R18") (pin "1") (pinfunction "1_1") (pintype "passive"))
      (node (ref "U4") (pin "61") (pinfunction "LED_2_61") (pintype "bidirectional"))
    )
    (net (code "57") (name "PHY_MDC") (class "Default")
      (node (ref "J1") (pin "53") (pinfunction "53_53") (pintype "passive"))
      (node (ref "U4") (pin "20") (pinfunction "MDC_20") (pintype "input"))
    )
    (net (code "58") (name "PHY_MDIO") (class "Default")
      (node (ref "J1") (pin "51") (pinfunction "51_51") (pintype "passive"))
      (node (ref "R26") (pin "2") (pinfunction "2_2") (pintype "passive"))
      (node (ref "U4") (pin "21") (pinfunction "MDIO_21") (pintype "bidirectional"))
    )
    (net (code "59") (name "PHY_RST") (class "Default")
      (node (ref "J1") (pin "5") (pinfunction "5_5") (pintype "passive"))
      (node (ref "U4") (pin "59") (pinfunction "RESET_N_59") (pintype "input"))
    )
    (net (code "60") (name "PHY_RX0") (class "Default")
      (node (ref "J1") (pin "30") (pinfunction "30_30") (pintype "passive"))
      (node (ref "U4") (pin "44") (pinfunction "RX_D0_44") (pintype "output"))
    )
    (net (code "61") (name "PHY_RX1") (class "Default")
      (node (ref "J1") (pin "29") (pinfunction "29_29") (pintype "passive"))
      (node (ref "U4") (pin "45") (pinfunction "RX_D1_45") (pintype "output"))
    )
    (net (code "62") (name "PHY_RX2") (class "Default")
      (node (ref "J1") (pin "28") (pinfunction "28_28") (pintype "passive"))
      (node (ref "U4") (pin "46") (pinfunction "RX_D2_46") (pintype "output"))
    )
    (net (code "63") (name "PHY_RX3") (class "Default")
      (node (ref "J1") (pin "27") (pinfunction "27_27") (pintype "passive"))
      (node (ref "U4") (pin "47") (pinfunction "RX_D3_47") (pintype "output"))
    )
    (net (code "64") (name "PHY_RX4") (class "Default")
      (node (ref "J1") (pin "24") (pinfunction "24_24") (pintype "passive"))
      (node (ref "U4") (pin "48") (pinfunction "RX_D4_GPIO_48") (pintype "bidirectional"))
    )
    (net (code "65") (name "PHY_RX5") (class "Default")
      (node (ref "J1") (pin "16") (pinfunction "16_16") (pintype "passive"))
      (node (ref "U4") (pin "49") (pinfunction "RX_D5_GPIO_49") (pintype "bidirectional"))
    )
    (net (code "66") (name "PHY_RX6") (class "Default")
      (node (ref "J1") (pin "18") (pinfunction "18_18") (pintype "passive"))
      (node (ref "R24") (pin "2") (pinfunction "2_2") (pintype "passive"))
      (node (ref "R25") (pin "1") (pinfunction "1_1") (pintype "passive"))
      (node (ref "U4") (pin "50") (pinfunction "RX_D6_GPIO_50") (pintype "bidirectional"))
    )
    (net (code "67") (name "PHY_RX7") (class "Default")
      (node (ref "J1") (pin "22") (pinfunction "22_22") (pintype "passive"))
      (node (ref "U4") (pin "51") (pinfunction "RX_D7_GPIO_51") (pintype "bidirectional"))
    )
    (net (code "68") (name "PHY_RXCK") (class "Default")
      (node (ref "J1") (pin "33") (pinfunction "33_33") (pintype "passive"))
      (node (ref "U4") (pin "43") (pinfunction "RX_CLK_43") (pintype "output"))
    )
    (net (code "69") (name "PHY_RXCTL_DV") (class "Default")
      (node (ref "J1") (pin "10") (pinfunction "10_10") (pintype "passive"))
      (node (ref "R22") (pin "1") (pinfunction "1_1") (pintype "passive"))
      (node (ref "R23") (pin "2") (pinfunction "2_2") (pintype "passive"))
      (node (ref "U4") (pin "53") (pinfunction "RX_DV_RX_CTRL_53") (pintype "bidirectional"))
    )
    (net (code "70") (name "PHY_RX_ER") (class "Default")
      (node (ref "J1") (pin "6") (pinfunction "6_6") (pintype "passive"))
      (node (ref "U4") (pin "54") (pinfunction "RX_ER_GPIO_54") (pintype "bidirectional"))
    )
    (net (code "71") (name "PHY_TX0") (class "Default")
      (node (ref "J1") (pin "36") (pinfunction "36_36") (pintype "passive"))
      (node (ref "U4") (pin "38") (pinfunction "TX_D0_38") (pintype "input"))
    )
    (net (code "72") (name "PHY_TX1") (class "Default")
      (node (ref "J1") (pin "39") (pinfunction "39_39") (pintype "passive"))
      (node (ref "U4") (pin "37") (pinfunction "TX_D1_37") (pintype "input"))
    )
    (net (code "73") (name "PHY_TX2") (class "Default")
      (node (ref "J1") (pin "40") (pinfunction "40_40") (pintype "passive"))
      (node (ref "U4") (pin "36") (pinfunction "TX_D2_36") (pintype "input"))
    )
    (net (code "74") (name "PHY_TX3") (class "Default")
      (node (ref "J1") (pin "41") (pinfunction "41_41") (pintype "passive"))
      (node (ref "U4") (pin "35") (pinfunction "TX_D3_35") (pintype "input"))
    )
    (net (code "75") (name "PHY_TX4") (class "Default")
      (node (ref "J1") (pin "42") (pinfunction "42_42") (pintype "passive"))
      (node (ref "U4") (pin "34") (pinfunction "TX_D4_34") (pintype "input"))
    )
    (net (code "76") (name "PHY_TX5") (class "Default")
      (node (ref "J1") (pin "45") (pinfunction "45_45") (pintype "passive"))
      (node (ref "U4") (pin "33") (pinfunction "TX_D5_33") (pintype "input"))
    )
    (net (code "77") (name "PHY_TX6") (class "Default")
      (node (ref "J1") (pin "48") (pinfunction "48_48") (pintype "passive"))
      (node (ref "U4") (pin "32") (pinfunction "TX_D6_32") (pintype "input"))
    )
    (net (code "78") (name "PHY_TX7") (class "Default")
      (node (ref "J1") (pin "46") (pinfunction "46_46") (pintype "passive"))
      (node (ref "U4") (pin "31") (pinfunction "TX_D7_31") (pintype "input"))
    )
    (net (code "79") (name "PHY_TXCK") (class "Default")
      (node (ref "J1") (pin "34") (pinfunction "34_34") (pintype "passive"))
      (node (ref "U4") (pin "40") (pinfunction "GTX_CLK_40") (pintype "input"))
    )
    (net (code "80") (name "PHY_TXCK_10{slash}100") (class "Default")
      (node (ref "J1") (pin "52") (pinfunction "52_52") (pintype "passive"))
      (node (ref "U4") (pin "30") (pinfunction "TX_CLK_30") (pintype "output"))
    )
    (net (code "81") (name "PHY_TXCTL_DV") (class "Default")
      (node (ref "J1") (pin "12") (pinfunction "12_12") (pintype "passive"))
      (node (ref "U4") (pin "52") (pinfunction "TX_EN_TX_CTRL_52") (pintype "bidirectional"))
    )
    (net (code "82") (name "PHY_TX_ER") (class "Default")
      (node (ref "J1") (pin "35") (pinfunction "35_35") (pintype "passive"))
      (node (ref "U4") (pin "39") (pinfunction "TX_ER_39") (pintype "input"))
    )
    (net (code "83") (name "PHY_~{INT}_~{PWDN}") (class "Default")
      (node (ref "J1") (pin "3") (pinfunction "3_3") (pintype "passive"))
      (node (ref "R21") (pin "2") (pinfunction "2_2") (pintype "passive"))
      (node (ref "U4") (pin "60") (pinfunction "INT_PWDN_60") (pintype "bidirectional"))
    )
    (net (code "84") (name "POE+_MODE_A") (class "Default")
      (node (ref "C10") (pin "2") (pinfunction "2_2") (pintype "passive"))
      (node (ref "OUT") (pin "2") (pinfunction "2_2") (pintype "passive"))
      (node (ref "T1") (pin "22") (pinfunction "24_22") (pintype "bidirectional"))
    )
    (net (code "85") (name "POE+_MODE_B") (class "Default")
      (node (ref "C14") (pin "2") (pinfunction "2_2") (pintype "passive"))
      (node (ref "OUT") (pin "4") (pinfunction "4_4") (pintype "passive"))
      (node (ref "T1") (pin "16") (pinfunction "18_16") (pintype "bidirectional"))
    )
    (net (code "86") (name "POE-_MODE_A") (class "Default")
      (node (ref "C12") (pin "2") (pinfunction "2_2") (pintype "passive"))
      (node (ref "OUT") (pin "3") (pinfunction "3_3") (pintype "passive"))
      (node (ref "T1") (pin "21") (pinfunction "21_21") (pintype "bidirectional"))
    )
    (net (code "87") (name "POE-_MODE_B") (class "Default")
      (node (ref "C17") (pin "2") (pinfunction "2_2") (pintype "passive"))
      (node (ref "OUT") (pin "5") (pinfunction "5_5") (pintype "passive"))
      (node (ref "T1") (pin "15") (pinfunction "15_15") (pintype "bidirectional"))
    )
    (net (code "88") (name "VDDA1P8") (class "Default")
      (node (ref "U4") (pin "64") (pinfunction "VDDA1P8_64") (pintype "power_in"))
    )
    (net (code "89") (name "VDDA1P8_2") (class "Default")
      (node (ref "U4") (pin "17") (pinfunction "VDDA1P8_2_17") (pintype "power_in"))
    )
    (net (code "90") (name "unconnected-(J1-Pad4)") (class "Default")
      (node (ref "J1") (pin "4") (pinfunction "4_4") (pintype "passive"))
    )
    (net (code "91") (name "unconnected-(J1-Pad9)") (class "Default")
      (node (ref "J1") (pin "9") (pinfunction "9_9") (pintype "passive"))
    )
    (net (code "92") (name "unconnected-(J1-Pad11)") (class "Default")
      (node (ref "J1") (pin "11") (pinfunction "11_11") (pintype "passive"))
    )
    (net (code "93") (name "unconnected-(J1-Pad15)") (class "Default")
      (node (ref "J1") (pin "15") (pinfunction "15_15") (pintype "passive"))
    )
    (net (code "94") (name "unconnected-(J1-Pad17)") (class "Default")
      (node (ref "J1") (pin "17") (pinfunction "17_17") (pintype "passive"))
    )
    (net (code "95") (name "unconnected-(J1-Pad21)") (class "Default")
      (node (ref "J1") (pin "21") (pinfunction "21_21") (pintype "passive"))
    )
    (net (code "96") (name "unconnected-(J1-Pad23)") (class "Default")
      (node (ref "J1") (pin "23") (pinfunction "23_23") (pintype "passive"))
    )
    (net (code "97") (name "unconnected-(J1-Pad47)") (class "Default")
      (node (ref "J1") (pin "47") (pinfunction "47_47") (pintype "passive"))
    )
    (net (code "98") (name "unconnected-(J1-Pad54)") (class "Default")
      (node (ref "J1") (pin "54") (pinfunction "54_54") (pintype "passive"))
    )
    (net (code "99") (name "unconnected-(J1-Pad58)") (class "Default")
      (node (ref "J1") (pin "58") (pinfunction "58_58") (pintype "passive"))
    )
    (net (code "100") (name "unconnected-(J1-Pad61)") (class "Default")
      (node (ref "J1") (pin "61") (pinfunction "61_61") (pintype "passive"))
    )
    (net (code "101") (name "unconnected-(J1-Pad62)") (class "Default")
      (node (ref "J1") (pin "62") (pinfunction "62_62") (pintype "passive"))
    )
    (net (code "102") (name "unconnected-(J1-Pad63)") (class "Default")
      (node (ref "J1") (pin "63") (pinfunction "63_63") (pintype "passive"))
    )
    (net (code "103") (name "unconnected-(J1-Pad64)") (class "Default")
      (node (ref "J1") (pin "64") (pinfunction "64_64") (pintype "passive"))
    )
    (net (code "104") (name "unconnected-(U1-PG-Pad6)") (class "Default")
      (node (ref "U1") (pin "6") (pinfunction "PG_6") (pintype "bidirectional"))
    )
    (net (code "105") (name "unconnected-(U2-PG-Pad6)") (class "Default")
      (node (ref "U2") (pin "6") (pinfunction "PG_6") (pintype "bidirectional"))
    )
    (net (code "106") (name "unconnected-(U3-PG-Pad6)") (class "Default")
      (node (ref "U3") (pin "6") (pinfunction "PG_6") (pintype "bidirectional"))
    )
    (net (code "107") (name "unconnected-(U4-CLK_OUT-Pad22)") (class "Default")
      (node (ref "U4") (pin "22") (pinfunction "CLK_OUT_22") (pintype "output"))
    )
    (net (code "108") (name "unconnected-(U4-COL_GPIO-Pad55)") (class "Default")
      (node (ref "U4") (pin "55") (pinfunction "COL_GPIO_55") (pintype "output"))
    )
    (net (code "109") (name "unconnected-(U4-CRS_GPIO-Pad56)") (class "Default")
      (node (ref "U4") (pin "56") (pinfunction "CRS_GPIO_56") (pintype "bidirectional"))
    )
    (net (code "110") (name "unconnected-(U4-JTAG_CLK-Pad25)") (class "Default")
      (node (ref "U4") (pin "25") (pinfunction "JTAG_CLK_25") (pintype "input"))
    )
    (net (code "111") (name "unconnected-(U4-JTAG_TDI-Pad28)") (class "Default")
      (node (ref "U4") (pin "28") (pinfunction "JTAG_TDI_28") (pintype "input"))
    )
    (net (code "112") (name "unconnected-(U4-JTAG_TDO-Pad26)") (class "Default")
      (node (ref "U4") (pin "26") (pinfunction "JTAG_TDO_26") (pintype "output"))
    )
    (net (code "113") (name "unconnected-(U4-JTAG_TMS-Pad27)") (class "Default")
      (node (ref "U4") (pin "27") (pinfunction "JTAG_TMS_27") (pintype "input"))
    )
    (net (code "114") (name "unconnected-(U4-JTAG_TRSTN-Pad24)") (class "Default")
      (node (ref "U4") (pin "24") (pinfunction "JTAG_TRSTN_24") (pintype "input"))
    )
    (net (code "115") (name "unconnected-(U4-RESERVED-Pad16)") (class "Default")
      (node (ref "U4") (pin "16") (pinfunction "RESERVED_16") (pintype "passive"))
    )
    (net (code "116") (name "unconnected-(U4-RESERVED_2-Pad1)") (class "Default")
      (node (ref "U4") (pin "1") (pinfunction "RESERVED_2_1") (pintype "passive"))
    )
    (net (code "117") (name "unconnected-(U4-RESERVED_3-Pad7)") (class "Default")
      (node (ref "U4") (pin "7") (pinfunction "RESERVED_3_7") (pintype "passive"))
    )
    (net (code "118") (name "unconnected-(U4-RESERVED_4-Pad9)") (class "Default")
      (node (ref "U4") (pin "9") (pinfunction "RESERVED_4_9") (pintype "passive"))
    )
    (net (code "119") (name "unconnected-(U4-XO-Pad18)") (class "Default")
      (node (ref "U4") (pin "18") (pinfunction "XO_18") (pintype "passive"))
    )
  )
)
